# Magnetic_Sensor.net
KiCad netlist of a schematic drawn in Altium Designer
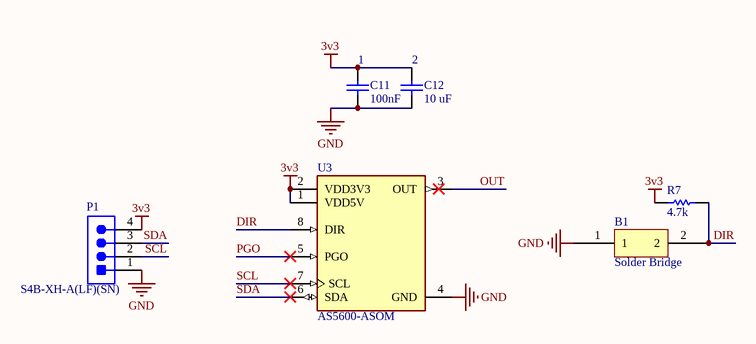
[diagram p0: Magnetic Sensor.SchDoc]

(export (version "E")
  (design (tool "Eeschema 10.0.6"))
  (components
    (comp (ref "B1")
      (value "Solder Bridge")
      (footprint "Solder Bridge")
      (libsource (lib "Main") (part "Solder Bridge"))
    )
    (comp (ref "C11") (value "100nF") (footprint "0402CAP") (libsource (lib "Main") (part "04023D104KAT2A")))
    (comp (ref "C12")
      (value "10 uF")
      (footprint "CAPC2013X140X50LL20T25")
      (fields
        (field (name "MANUFACTURER") "AVX Interconnect / Elco")
        (field (name "PART NUMBER") "0805ZC106KAT2A")
      )
      (libsource (lib "Main") (part "0805ZC106KAT2A"))
    )
    (comp (ref "P1")
      (value "S4B-XH-A(LF)(SN)")
      (footprint "JST-S4B-XH-A(LF)(SN)_V")
      (libsource (lib "Main") (part "S4B-XH-A(LF)(SN)"))
    )
    (comp (ref "R7")
      (value "4.7k")
      (footprint "RESC1005X40X25LL05T05")
      (description "Chip Resistor, 4.7 KOhm, +/- 1%, 0.1 W, -55 to 155 degC, 0402 (1005 Metric), RoHS, Tape and Reel")
      (fields (field (name "TOLERANCE") "1%") (field (name "PARTNUMBER") "ERJ-2RKF4701X"))
      (libsource (lib "Main") (part "ERJ-2RKF4701X"))
    )
    (comp (ref "U3")
      (value "AS5600-ASOM")
      (footprint "SOIC127P600X175-8N")
      (description "SENSOR ANGLE 360DEG SMD")
      (libsource (lib "Main") (part "AS5600-ASOM"))
    )
  )
  (nets
    (net (code "1") (name "/DIR") (class "Default")
      (node (ref "B1") (pin "2") (pinfunction "2_2") (pintype "passive"))
      (node (ref "R7") (pin "2") (pinfunction "2_2") (pintype "passive"))
      (node (ref "U3") (pin "8") (pinfunction "DIR_8") (pintype "input"))
    )
    (net (code "2") (name "/OUT") (class "Default")
      (node (ref "U3") (pin "3") (pinfunction "OUT_3") (pintype "output"))
    )
    (net (code "3") (name "/PGO") (class "Default")
      (node (ref "U3") (pin "5") (pinfunction "PGO_5") (pintype "input+no_connect"))
    )
    (net (code "4") (name "/SCL") (class "Default")
      (node (ref "P1") (pin "2") (pinfunction "2_2") (pintype "passive"))
      (node (ref "U3") (pin "7") (pinfunction "SCL_7") (pintype "input"))
    )
    (net (code "5") (name "/SDA") (class "Default")
      (node (ref "P1") (pin "3") (pinfunction "3_3") (pintype "passive"))
      (node (ref "U3") (pin "6") (pinfunction "SDA_6") (pintype "bidirectional"))
    )
    (net (code "6") (name "3v3") (class "Default")
      (node (ref "C11") (pin "2") (pinfunction "2_2") (pintype "passive"))
      (node (ref "C12") (pin "2") (pinfunction "2_2") (pintype "passive"))
      (node (ref "P1") (pin "4") (pinfunction "4_4") (pintype "passive"))
      (node (ref "R7") (pin "1") (pinfunction "1_1") (pintype "passive"))
      (node (ref "U3") (pin "1") (pinfunction "VDD5V_1") (pintype "power_in"))
      (node (ref "U3") (pin "2") (pinfunction "VDD3V3_2") (pintype "power_in"))
    )
    (net (code "7") (name "GND") (class "Default")
      (node (ref "B1") (pin "1") (pinfunction "1_1") (pintype "passive"))
      (node (ref "C11") (pin "1") (pinfunction "1_1") (pintype "passive"))
      (node (ref "C12") (pin "1") (pinfunction "1_1") (pintype "passive"))
      (node (ref "P1") (pin "1") (pinfunction "1_1") (pintype "passive"))
      (node (ref "U3") (pin "4") (pinfunction "GND_4") (pintype "power_in"))
    )
  )
)
